# IgniterDriver.net
KiCad netlist of a schematic drawn in EAGLE
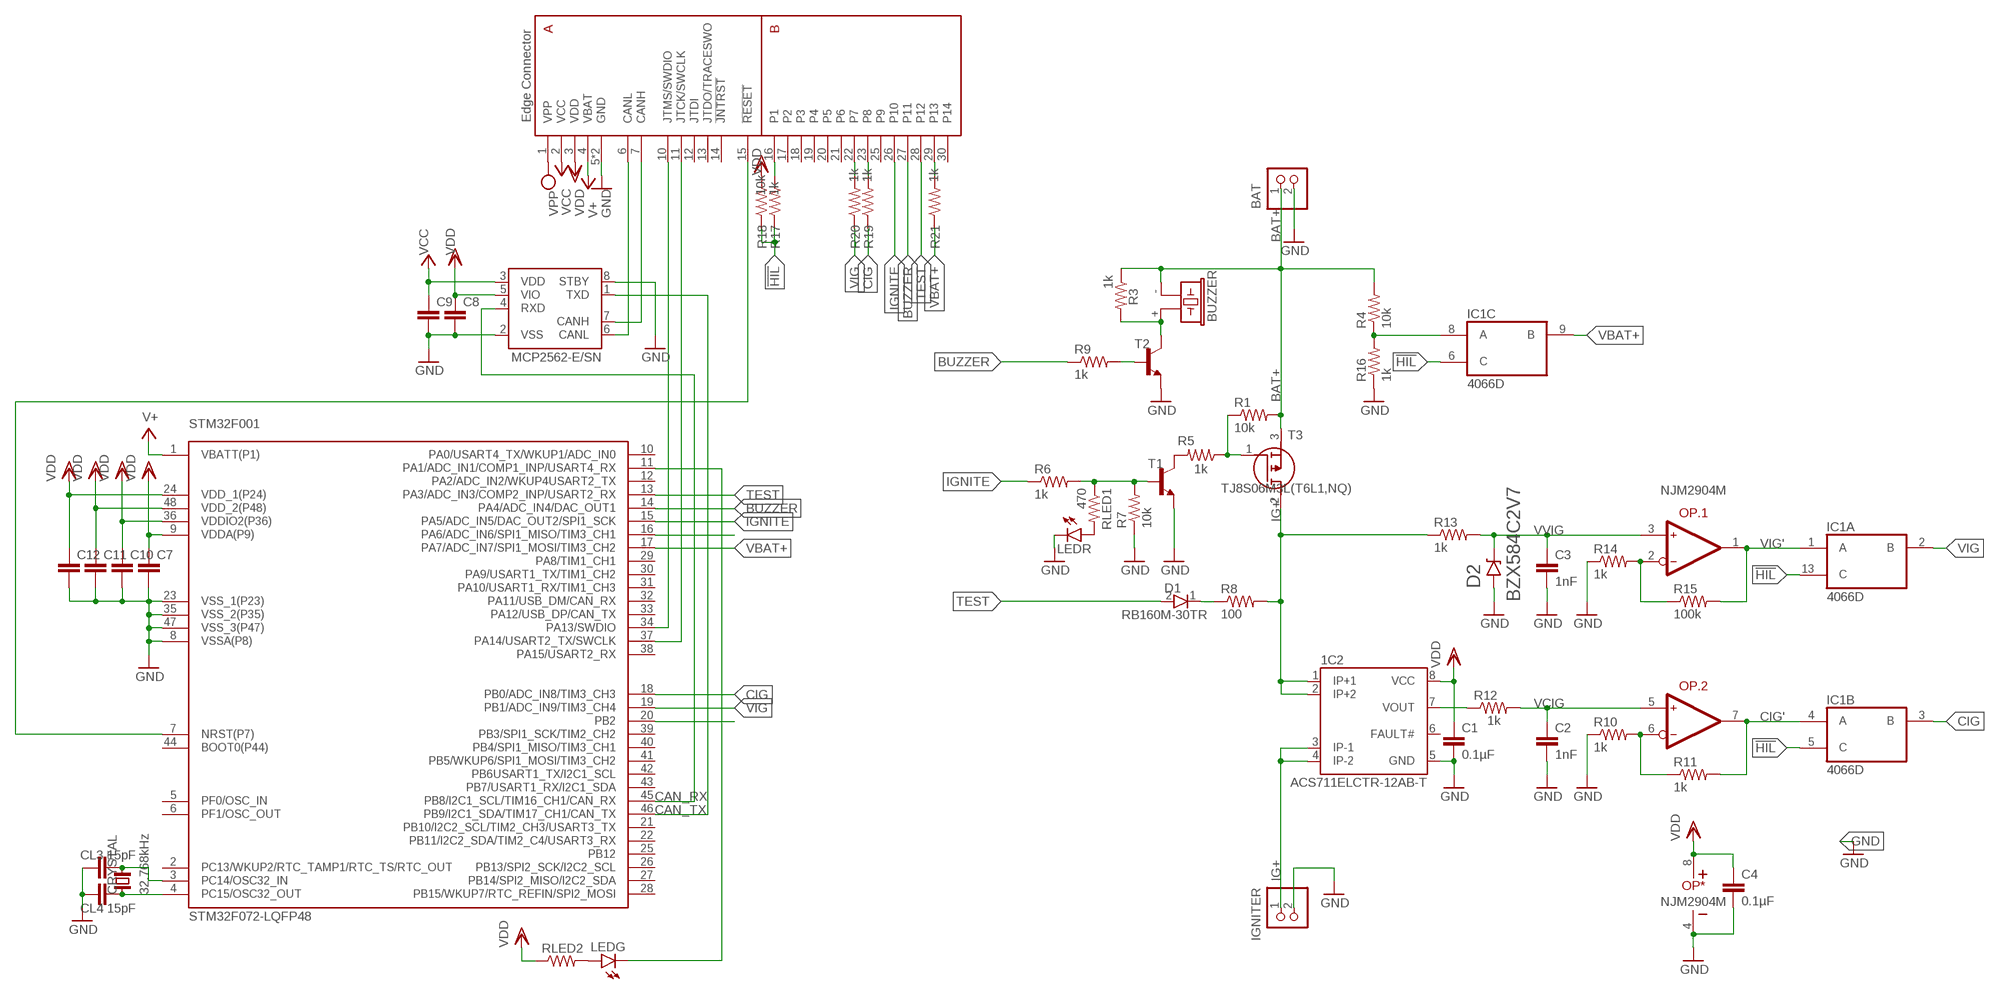
[diagram p0: schematic, sheet 1]

(export (version "E")
  (design (tool "Eeschema 10.0.6"))
  (components
    (comp (ref "1C2")
      (value "ACS711ELCTR-12AB-T")
      (footprint "eagle-import:SOIC8")
      (libsource (lib "eagle-import") (part "ACS711ELC?TR-12AB-T"))
    )
    (comp (ref "BAT")
      (value "S2B-XH-A")
      (footprint "eagle-import:S2B-XH-A")
      (libsource (lib "eagle-import") (part "S2B-XH-A"))
    )
    (comp (ref "BUZZER")
      (value "F/CM12P")
      (footprint "eagle-import:F_CM12P")
      (libsource (lib "eagle-import") (part "F/CM12P"))
    )
    (comp (ref "C1")
      (value "0.1µF")
      (footprint "eagle-import:C0603K")
      (libsource (lib "eagle-import") (part "C-EUC0603K"))
    )
    (comp (ref "C2")
      (value "1nF")
      (footprint "eagle-import:C0603K")
      (libsource (lib "eagle-import") (part "C-EUC0603K"))
    )
    (comp (ref "C3")
      (value "1nF")
      (footprint "eagle-import:C0603K")
      (libsource (lib "eagle-import") (part "C-EUC0603K"))
    )
    (comp (ref "C4")
      (value "0.1µF")
      (footprint "eagle-import:C0603K")
      (libsource (lib "eagle-import") (part "C-EUC0603K"))
    )
    (comp (ref "C7")
      (value "C-EUC0603K")
      (footprint "eagle-import:C0603K")
      (libsource (lib "eagle-import") (part "C-EUC0603K"))
    )
    (comp (ref "C8")
      (value "C-EUC0603K")
      (footprint "eagle-import:C0603K")
      (libsource (lib "eagle-import") (part "C-EUC0603K"))
    )
    (comp (ref "C9")
      (value "C-EUC0603K")
      (footprint "eagle-import:C0603K")
      (libsource (lib "eagle-import") (part "C-EUC0603K"))
    )
    (comp (ref "C10")
      (value "C-EUC0603K")
      (footprint "eagle-import:C0603K")
      (libsource (lib "eagle-import") (part "C-EUC0603K"))
    )
    (comp (ref "C11")
      (value "C-EUC0603K")
      (footprint "eagle-import:C0603K")
      (libsource (lib "eagle-import") (part "C-EUC0603K"))
    )
    (comp (ref "C12")
      (value "C-EUC0603K")
      (footprint "eagle-import:C0603K")
      (libsource (lib "eagle-import") (part "C-EUC0603K"))
    )
    (comp (ref "CL3")
      (value "15pF")
      (footprint "eagle-import:C0603K")
      (libsource (lib "eagle-import") (part "C-EUC0603K"))
    )
    (comp (ref "CL4")
      (value "15pF")
      (footprint "eagle-import:C0603K")
      (libsource (lib "eagle-import") (part "C-EUC0603K"))
    )
    (comp (ref "CRYSTAL")
      (value "32.768kHz")
      (footprint "eagle-import:FC-255")
      (libsource (lib "eagle-import") (part "CRYTALFC-255"))
    )
    (comp (ref "D1")
      (value "RB160M-30TR")
      (footprint "eagle-import:SODFL3516X90N")
      (fields (field (name "MOUSER_PART_NUMBER") "755-RB160M-30TR") (field (name "RS_PART_NUMBER") "7526079"))
      (libsource (lib "eagle-import") (part "RB160M-30TR"))
    )
    (comp (ref "D2")
      (value "BZX584C2V7")
      (footprint "eagle-import:BZX584C")
      (libsource (lib "eagle-import") (part "BZX584C"))
    )
    (comp (ref "IC1")
      (value "4066D")
      (footprint "eagle-import:SO14")
      (libsource (lib "eagle-import") (part "4066D"))
    )
    (comp (ref "IGNITER")
      (value "S2B-XH-A")
      (footprint "eagle-import:S2B-XH-A")
      (libsource (lib "eagle-import") (part "S2B-XH-A"))
    )
    (comp (ref "LEDG")
      (value "LEDCHIP-LED0603")
      (footprint "eagle-import:CHIP-LED0603")
      (libsource (lib "eagle-import") (part "LEDCHIP-LED0603"))
    )
    (comp (ref "LEDR")
      (value "LEDCHIPLED_0603")
      (footprint "eagle-import:CHIPLED_0603")
      (libsource (lib "eagle-import") (part "LEDCHIPLED_0603"))
    )
    (comp (ref "MCP2562")
      (value "MCP2562-E/SN")
      (footprint "eagle-import:SOIC127P600X175-8N")
      (fields (field (name "MF") "Microchip"))
      (libsource (lib "eagle-import") (part "MCP2562-E/SN"))
    )
    (comp (ref "OP")
      (value "NJM2904M")
      (footprint "eagle-import:SO-8")
      (libsource (lib "eagle-import") (part "NJM2904M"))
    )
    (comp (ref "R1")
      (value "10k")
      (footprint "eagle-import:R0603")
      (libsource (lib "eagle-import") (part "R-US_R0603"))
    )
    (comp (ref "R3")
      (value "1k")
      (footprint "eagle-import:R0603")
      (libsource (lib "eagle-import") (part "R-US_R0603"))
    )
    (comp (ref "R4")
      (value "10k")
      (footprint "eagle-import:R0603")
      (libsource (lib "eagle-import") (part "R-US_R0603"))
    )
    (comp (ref "R5")
      (value "1k")
      (footprint "eagle-import:R0603")
      (libsource (lib "eagle-import") (part "R-US_R0603"))
    )
    (comp (ref "R6")
      (value "1k")
      (footprint "eagle-import:R0603")
      (libsource (lib "eagle-import") (part "R-US_R0603"))
    )
    (comp (ref "R7")
      (value "10k")
      (footprint "eagle-import:R0603")
      (libsource (lib "eagle-import") (part "R-US_R0603"))
    )
    (comp (ref "R8")
      (value "100")
      (footprint "eagle-import:R0603")
      (libsource (lib "eagle-import") (part "R-US_R0603"))
    )
    (comp (ref "R9")
      (value "1k")
      (footprint "eagle-import:R0603")
      (libsource (lib "eagle-import") (part "R-US_R0603"))
    )
    (comp (ref "R10")
      (value "1k")
      (footprint "eagle-import:R0603")
      (libsource (lib "eagle-import") (part "R-US_R0603"))
    )
    (comp (ref "R11")
      (value "1k")
      (footprint "eagle-import:R0603")
      (libsource (lib "eagle-import") (part "R-US_R0603"))
    )
    (comp (ref "R12")
      (value "1k")
      (footprint "eagle-import:R0603")
      (libsource (lib "eagle-import") (part "R-US_R0603"))
    )
    (comp (ref "R13")
      (value "1k")
      (footprint "eagle-import:R0603")
      (libsource (lib "eagle-import") (part "R-US_R0603"))
    )
    (comp (ref "R14")
      (value "1k")
      (footprint "eagle-import:R0603")
      (libsource (lib "eagle-import") (part "R-US_R0603"))
    )
    (comp (ref "R15")
      (value "100k")
      (footprint "eagle-import:R0603")
      (libsource (lib "eagle-import") (part "R-US_R0603"))
    )
    (comp (ref "R16")
      (value "1k")
      (footprint "eagle-import:R0603")
      (libsource (lib "eagle-import") (part "R-US_R0603"))
    )
    (comp (ref "R17")
      (value "1k")
      (footprint "eagle-import:R0603")
      (libsource (lib "eagle-import") (part "R-US_R0603"))
    )
    (comp (ref "R18")
      (value "10k")
      (footprint "eagle-import:R0603")
      (libsource (lib "eagle-import") (part "R-US_R0603"))
    )
    (comp (ref "R19")
      (value "1k")
      (footprint "eagle-import:R0603")
      (libsource (lib "eagle-import") (part "resistor_348_R-US_R0603"))
    )
    (comp (ref "R20")
      (value "1k")
      (footprint "eagle-import:R0603")
      (libsource (lib "eagle-import") (part "resistor_348_R-US_R0603"))
    )
    (comp (ref "R21")
      (value "1k")
      (footprint "eagle-import:R0603")
      (libsource (lib "eagle-import") (part "resistor_348_R-US_R0603"))
    )
    (comp (ref "RLED1")
      (value "470")
      (footprint "eagle-import:R0603")
      (libsource (lib "eagle-import") (part "R-US_R0603"))
    )
    (comp (ref "RLED2")
      (value "R-US_R0603")
      (footprint "eagle-import:R0603")
      (libsource (lib "eagle-import") (part "R-US_R0603"))
    )
    (comp (ref "STM32F001")
      (value "STM32F072-LQFP48")
      (footprint "eagle-import:LQFP48")
      (libsource (lib "eagle-import") (part "STM32F072-LQFP48"))
    )
    (comp (ref "T1")
      (value "-NPN-SOT23-EBC")
      (footprint "eagle-import:SOT23-EBC")
      (libsource (lib "eagle-import") (part "-NPN-SOT23-EBC"))
    )
    (comp (ref "T2")
      (value "-NPN-SOT23-EBC")
      (footprint "eagle-import:SOT23-EBC")
      (libsource (lib "eagle-import") (part "-NPN-SOT23-EBC"))
    )
    (comp (ref "T3")
      (value "TJ8S06M3L(T6L1,NQ)")
      (footprint "eagle-import:TJ8S06M3LT6L1NQ")
      (fields (field (name "MOUSER_PART_NUMBER") "757-TJ8S06M3LT6L1NQ"))
      (libsource (lib "eagle-import") (part "TJ8S06M3L(T6L1,NQ)"))
    )
    (comp (ref "U$2")
      (value "EDGE30")
      (footprint "eagle-import:EDGE30")
      (libsource (lib "eagle-import") (part "EDGE30"))
    )
  )
  (nets
    (net (code "1") (name "/BAT+") (class "Default")
      (node (ref "BAT") (pin "1") (pinfunction "1_1") (pintype "passive"))
      (node (ref "BUZZER") (pin "-") (pinfunction "2_-") (pintype "passive"))
      (node (ref "R1") (pin "2") (pinfunction "2_2") (pintype "passive"))
      (node (ref "R3") (pin "1") (pinfunction "1_1") (pintype "passive"))
      (node (ref "R4") (pin "2") (pinfunction "2_2") (pintype "passive"))
      (node (ref "T3") (pin "3") (pinfunction "S_3") (pintype "bidirectional"))
    )
    (net (code "2") (name "/CAN_RX") (class "Default")
      (node (ref "MCP2562") (pin "4") (pinfunction "RXD_4") (pintype "output"))
      (node (ref "STM32F001") (pin "45") (pinfunction "PB8/I2C1_SCL/TIM16_CH1/CAN_RX_45") (pintype "bidirectional"))
    )
    (net (code "3") (name "/CAN_TX") (class "Default")
      (node (ref "MCP2562") (pin "1") (pinfunction "TXD_1") (pintype "input"))
      (node (ref "STM32F001") (pin "46") (pinfunction "PB9/I2C1_SDA/TIM17_CH1/CAN_TX_46") (pintype "bidirectional"))
    )
    (net (code "4") (name "/CIG'") (class "Default")
      (node (ref "IC1") (pin "4") (pinfunction "A_4") (pintype "tri_state"))
      (node (ref "OP") (pin "7") (pinfunction "OUT_7") (pintype "output"))
      (node (ref "R11") (pin "2") (pinfunction "2_2") (pintype "passive"))
    )
    (net (code "5") (name "/IG+") (class "Default")
      (node (ref "1C2") (pin "3") (pinfunction "IP-1_3") (pintype "bidirectional"))
      (node (ref "1C2") (pin "4") (pinfunction "IP-2_4") (pintype "bidirectional"))
      (node (ref "IGNITER") (pin "1") (pinfunction "1_1") (pintype "passive"))
    )
    (net (code "6") (name "/IG+'") (class "Default")
      (node (ref "1C2") (pin "1") (pinfunction "IP+1_1") (pintype "bidirectional"))
      (node (ref "1C2") (pin "2") (pinfunction "IP+2_2") (pintype "bidirectional"))
      (node (ref "R13") (pin "1") (pinfunction "1_1") (pintype "passive"))
      (node (ref "R8") (pin "2") (pinfunction "2_2") (pintype "passive"))
      (node (ref "T3") (pin "2") (pinfunction "D_2") (pintype "bidirectional"))
    )
    (net (code "7") (name "/VCIG") (class "Default")
      (node (ref "C2") (pin "1") (pinfunction "1_1") (pintype "passive"))
      (node (ref "OP") (pin "5") (pinfunction "IN+_5") (pintype "input"))
      (node (ref "R12") (pin "2") (pinfunction "2_2") (pintype "passive"))
    )
    (net (code "8") (name "/VIG'") (class "Default")
      (node (ref "IC1") (pin "1") (pinfunction "A_1") (pintype "tri_state"))
      (node (ref "OP") (pin "1") (pinfunction "OUT_1") (pintype "output"))
      (node (ref "R15") (pin "2") (pinfunction "2_2") (pintype "passive"))
    )
    (net (code "9") (name "/VVIG") (class "Default")
      (node (ref "C3") (pin "1") (pinfunction "1_1") (pintype "passive"))
      (node (ref "D2") (pin "C") (pinfunction "C_C") (pintype "bidirectional"))
      (node (ref "OP") (pin "3") (pinfunction "IN+_3") (pintype "input"))
      (node (ref "R13") (pin "2") (pinfunction "2_2") (pintype "passive"))
    )
    (net (code "10") (name "/~{HIL}") (class "Default")
      (node (ref "IC1") (pin "13") (pinfunction "C_13") (pintype "input"))
      (node (ref "IC1") (pin "5") (pinfunction "C_5") (pintype "input"))
      (node (ref "IC1") (pin "6") (pinfunction "C_6") (pintype "input"))
      (node (ref "R17") (pin "1") (pinfunction "1_1") (pintype "passive"))
      (node (ref "R18") (pin "1") (pinfunction "1_1") (pintype "passive"))
    )
    (net (code "11") (name "BUZZER") (class "Default")
      (node (ref "R9") (pin "1") (pinfunction "1_1") (pintype "passive"))
      (node (ref "STM32F001") (pin "14") (pinfunction "PA4/ADC_IN4/DAC_OUT1_14") (pintype "bidirectional"))
      (node (ref "U$2") (pin "27") (pinfunction "P11_27") (pintype "bidirectional"))
    )
    (net (code "12") (name "CIG") (class "Default")
      (node (ref "IC1") (pin "3") (pinfunction "B_3") (pintype "tri_state"))
      (node (ref "R19") (pin "1") (pinfunction "1_1") (pintype "passive"))
      (node (ref "STM32F001") (pin "18") (pinfunction "PB0/ADC_IN8/TIM3_CH3_18") (pintype "bidirectional"))
    )
    (net (code "13") (name "GND") (class "Default")
      (node (ref "1C2") (pin "5") (pinfunction "GND_5") (pintype "bidirectional"))
      (node (ref "BAT") (pin "2") (pinfunction "2_2") (pintype "passive"))
      (node (ref "C1") (pin "2") (pinfunction "2_2") (pintype "passive"))
      (node (ref "C10") (pin "2") (pinfunction "2_2") (pintype "passive"))
      (node (ref "C11") (pin "2") (pinfunction "2_2") (pintype "passive"))
      (node (ref "C12") (pin "2") (pinfunction "2_2") (pintype "passive"))
      (node (ref "C2") (pin "2") (pinfunction "2_2") (pintype "passive"))
      (node (ref "C3") (pin "2") (pinfunction "2_2") (pintype "passive"))
      (node (ref "C4") (pin "2") (pinfunction "2_2") (pintype "passive"))
      (node (ref "C7") (pin "2") (pinfunction "2_2") (pintype "passive"))
      (node (ref "C8") (pin "2") (pinfunction "2_2") (pintype "passive"))
      (node (ref "C9") (pin "2") (pinfunction "2_2") (pintype "passive"))
      (node (ref "CL3") (pin "1") (pinfunction "1_1") (pintype "passive"))
      (node (ref "CL4") (pin "1") (pinfunction "1_1") (pintype "passive"))
      (node (ref "D2") (pin "A") (pinfunction "A_A") (pintype "bidirectional"))
      (node (ref "IGNITER") (pin "2") (pinfunction "2_2") (pintype "passive"))
      (node (ref "LEDR") (pin "C") (pinfunction "C_C") (pintype "passive"))
      (node (ref "MCP2562") (pin "2") (pinfunction "VSS_2") (pintype "power_in"))
      (node (ref "MCP2562") (pin "8") (pinfunction "STBY_8") (pintype "input"))
      (node (ref "OP") (pin "4") (pinfunction "V-_4") (pintype "power_in"))
      (node (ref "R10") (pin "1") (pinfunction "1_1") (pintype "passive"))
      (node (ref "R14") (pin "1") (pinfunction "1_1") (pintype "passive"))
      (node (ref "R16") (pin "1") (pinfunction "1_1") (pintype "passive"))
      (node (ref "R7") (pin "1") (pinfunction "1_1") (pintype "passive"))
      (node (ref "STM32F001") (pin "23") (pinfunction "VSS_1(P23)_23") (pintype "bidirectional"))
      (node (ref "STM32F001") (pin "35") (pinfunction "VSS_2(P35)_35") (pintype "bidirectional"))
      (node (ref "STM32F001") (pin "47") (pinfunction "VSS_3(P47)_47") (pintype "bidirectional"))
      (node (ref "STM32F001") (pin "8") (pinfunction "VSSA(P8)_8") (pintype "bidirectional"))
      (node (ref "T1") (pin "E") (pinfunction "E_E") (pintype "passive"))
      (node (ref "T2") (pin "E") (pinfunction "E_E") (pintype "passive"))
      (node (ref "U$2") (pin "5") (pinfunction "GND_5") (pintype "power_in"))
      (node (ref "U$2") (pin "8") (pinfunction "GND_8") (pintype "power_in"))
    )
    (net (code "14") (name "IGNITE") (class "Default")
      (node (ref "R6") (pin "1") (pinfunction "1_1") (pintype "passive"))
      (node (ref "STM32F001") (pin "15") (pinfunction "PA5/ADC_IN5/DAC_OUT2/SPI1_SCK_15") (pintype "bidirectional"))
      (node (ref "U$2") (pin "26") (pinfunction "P10_26") (pintype "bidirectional"))
    )
    (net (code "15") (name "Net-(1C2-VOUT)") (class "Default")
      (node (ref "1C2") (pin "7") (pinfunction "VOUT_7") (pintype "bidirectional"))
      (node (ref "R12") (pin "1") (pinfunction "1_1") (pintype "passive"))
    )
    (net (code "16") (name "Net-(BUZZER-1)") (class "Default")
      (node (ref "BUZZER") (pin "+") (pinfunction "1_+") (pintype "passive"))
      (node (ref "R3") (pin "2") (pinfunction "2_2") (pintype "passive"))
      (node (ref "T2") (pin "C") (pinfunction "C_C") (pintype "passive"))
    )
    (net (code "17") (name "Net-(D1-K)") (class "Default")
      (node (ref "D1") (pin "1") (pinfunction "K_1") (pintype "bidirectional"))
      (node (ref "R8") (pin "1") (pinfunction "1_1") (pintype "passive"))
    )
    (net (code "18") (name "Net-(IC1C-A)") (class "Default")
      (node (ref "IC1") (pin "8") (pinfunction "A_8") (pintype "tri_state"))
      (node (ref "R16") (pin "2") (pinfunction "2_2") (pintype "passive"))
      (node (ref "R4") (pin "1") (pinfunction "1_1") (pintype "passive"))
    )
    (net (code "19") (name "Net-(LEDG-PadA)") (class "Default")
      (node (ref "LEDG") (pin "A") (pinfunction "A_A") (pintype "passive"))
      (node (ref "RLED2") (pin "2") (pinfunction "2_2") (pintype "passive"))
    )
    (net (code "20") (name "Net-(LEDR-PadA)") (class "Default")
      (node (ref "LEDR") (pin "A") (pinfunction "A_A") (pintype "passive"))
      (node (ref "RLED1") (pin "2") (pinfunction "2_2") (pintype "passive"))
    )
    (net (code "21") (name "Net-(MCP2562-CANH)") (class "Default")
      (node (ref "MCP2562") (pin "7") (pinfunction "CANH_7") (pintype "input"))
      (node (ref "U$2") (pin "7") (pinfunction "CANH_7") (pintype "bidirectional"))
    )
    (net (code "22") (name "Net-(MCP2562-CANL)") (class "Default")
      (node (ref "MCP2562") (pin "6") (pinfunction "CANL_6") (pintype "input"))
      (node (ref "U$2") (pin "6") (pinfunction "CANL_6") (pintype "bidirectional"))
    )
    (net (code "23") (name "Net-(OPB-IN-)") (class "Default")
      (node (ref "OP") (pin "2") (pinfunction "IN-_2") (pintype "input"))
      (node (ref "R14") (pin "2") (pinfunction "2_2") (pintype "passive"))
      (node (ref "R15") (pin "1") (pinfunction "1_1") (pintype "passive"))
    )
    (net (code "24") (name "Net-(OPC-IN-)") (class "Default")
      (node (ref "OP") (pin "6") (pinfunction "IN-_6") (pintype "input"))
      (node (ref "R10") (pin "2") (pinfunction "2_2") (pintype "passive"))
      (node (ref "R11") (pin "1") (pinfunction "1_1") (pintype "passive"))
    )
    (net (code "25") (name "Net-(R5-Pad2)") (class "Default")
      (node (ref "R5") (pin "2") (pinfunction "2_2") (pintype "passive"))
      (node (ref "T1") (pin "C") (pinfunction "C_C") (pintype "passive"))
    )
    (net (code "26") (name "Net-(R6-Pad2)") (class "Default")
      (node (ref "R6") (pin "2") (pinfunction "2_2") (pintype "passive"))
      (node (ref "R7") (pin "2") (pinfunction "2_2") (pintype "passive"))
      (node (ref "RLED1") (pin "1") (pinfunction "1_1") (pintype "passive"))
      (node (ref "T1") (pin "B") (pinfunction "B_B") (pintype "passive"))
    )
    (net (code "27") (name "Net-(R9-Pad2)") (class "Default")
      (node (ref "R9") (pin "2") (pinfunction "2_2") (pintype "passive"))
      (node (ref "T2") (pin "B") (pinfunction "B_B") (pintype "passive"))
    )
    (net (code "28") (name "Net-(STM32F001-NRST(P7))") (class "Default")
      (node (ref "STM32F001") (pin "7") (pinfunction "NRST(P7)_7") (pintype "bidirectional"))
      (node (ref "U$2") (pin "15") (pinfunction "~{RESET}_15") (pintype "bidirectional"))
    )
    (net (code "29") (name "Net-(STM32F001-PA1{slash}ADC_IN1{slash}COMP1_INP{slash}USART4_RX)") (class "Default")
      (node (ref "LEDG") (pin "C") (pinfunction "C_C") (pintype "passive"))
      (node (ref "STM32F001") (pin "11") (pinfunction "PA1/ADC_IN1/COMP1_INP/USART4_RX_11") (pintype "bidirectional"))
    )
    (net (code "30") (name "Net-(STM32F001-PA13{slash}SWDIO)") (class "Default")
      (node (ref "STM32F001") (pin "34") (pinfunction "PA13/SWDIO_34") (pintype "bidirectional"))
      (node (ref "U$2") (pin "10") (pinfunction "JTMS/SWDIO_10") (pintype "bidirectional"))
    )
    (net (code "31") (name "Net-(STM32F001-PA14{slash}USART2_TX{slash}SWCLK)") (class "Default")
      (node (ref "STM32F001") (pin "37") (pinfunction "PA14/USART2_TX/SWCLK_37") (pintype "bidirectional"))
      (node (ref "U$2") (pin "11") (pinfunction "JTCK/SWCLK_11") (pintype "bidirectional"))
    )
    (net (code "32") (name "Net-(STM32F001-PC14{slash}OSC32_IN)") (class "Default")
      (node (ref "CL3") (pin "2") (pinfunction "2_2") (pintype "passive"))
      (node (ref "CRYSTAL") (pin "2") (pinfunction "2_2") (pintype "passive"))
      (node (ref "STM32F001") (pin "3") (pinfunction "PC14/OSC32_IN_3") (pintype "bidirectional"))
    )
    (net (code "33") (name "Net-(STM32F001-PC15{slash}OSC32_OUT)") (class "Default")
      (node (ref "CL4") (pin "2") (pinfunction "2_2") (pintype "passive"))
      (node (ref "CRYSTAL") (pin "1") (pinfunction "1_1") (pintype "passive"))
      (node (ref "STM32F001") (pin "4") (pinfunction "PC15/OSC32_OUT_4") (pintype "bidirectional"))
    )
    (net (code "34") (name "Net-(T3-G)") (class "Default")
      (node (ref "R1") (pin "1") (pinfunction "1_1") (pintype "passive"))
      (node (ref "R5") (pin "1") (pinfunction "1_1") (pintype "passive"))
      (node (ref "T3") (pin "1") (pinfunction "G_1") (pintype "bidirectional"))
    )
    (net (code "35") (name "Net-(U$2-P1)") (class "Default")
      (node (ref "R17") (pin "2") (pinfunction "2_2") (pintype "passive"))
      (node (ref "U$2") (pin "16") (pinfunction "P1_16") (pintype "bidirectional"))
    )
    (net (code "36") (name "Net-(U$2-P7)") (class "Default")
      (node (ref "R20") (pin "2") (pinfunction "2_2") (pintype "passive"))
      (node (ref "U$2") (pin "22") (pinfunction "P7_22") (pintype "bidirectional"))
    )
    (net (code "37") (name "Net-(U$2-P8)") (class "Default")
      (node (ref "R19") (pin "2") (pinfunction "2_2") (pintype "passive"))
      (node (ref "U$2") (pin "23") (pinfunction "P8_23") (pintype "bidirectional"))
    )
    (net (code "38") (name "Net-(U$2-P13)") (class "Default")
      (node (ref "R21") (pin "2") (pinfunction "2_2") (pintype "passive"))
      (node (ref "U$2") (pin "29") (pinfunction "P13_29") (pintype "bidirectional"))
    )
    (net (code "39") (name "TEST") (class "Default")
      (node (ref "D1") (pin "2") (pinfunction "A_2") (pintype "bidirectional"))
      (node (ref "STM32F001") (pin "13") (pinfunction "PA3/ADC_IN3/COMP2_INP/USART2_RX_13") (pintype "bidirectional"))
      (node (ref "U$2") (pin "28") (pinfunction "P12_28") (pintype "bidirectional"))
    )
    (net (code "40") (name "V+") (class "Default")
      (node (ref "STM32F001") (pin "1") (pinfunction "VBATT(P1)_1") (pintype "bidirectional"))
      (node (ref "U$2") (pin "4") (pinfunction "VBAT_4") (pintype "power_in"))
    )
    (net (code "41") (name "VBAT+") (class "Default")
      (node (ref "IC1") (pin "9") (pinfunction "B_9") (pintype "tri_state"))
      (node (ref "R21") (pin "1") (pinfunction "1_1") (pintype "passive"))
      (node (ref "STM32F001") (pin "17") (pinfunction "PA7/ADC_IN7/SPI1_MOSI/TIM3_CH2_17") (pintype "bidirectional"))
    )
    (net (code "42") (name "VCC") (class "Default")
      (node (ref "C9") (pin "1") (pinfunction "1_1") (pintype "passive"))
      (node (ref "MCP2562") (pin "3") (pinfunction "VDD_3") (pintype "power_in"))
      (node (ref "U$2") (pin "2") (pinfunction "VCC_2") (pintype "power_in"))
    )
    (net (code "43") (name "VDD") (class "Default")
      (node (ref "1C2") (pin "8") (pinfunction "VCC_8") (pintype "bidirectional"))
      (node (ref "C1") (pin "1") (pinfunction "1_1") (pintype "passive"))
      (node (ref "C10") (pin "1") (pinfunction "1_1") (pintype "passive"))
      (node (ref "C11") (pin "1") (pinfunction "1_1") (pintype "passive"))
      (node (ref "C12") (pin "1") (pinfunction "1_1") (pintype "passive"))
      (node (ref "C4") (pin "1") (pinfunction "1_1") (pintype "passive"))
      (node (ref "C7") (pin "1") (pinfunction "1_1") (pintype "passive"))
      (node (ref "C8") (pin "1") (pinfunction "1_1") (pintype "passive"))
      (node (ref "MCP2562") (pin "5") (pinfunction "VIO_5") (pintype "power_in"))
      (node (ref "OP") (pin "8") (pinfunction "V+_8") (pintype "power_in"))
      (node (ref "R18") (pin "2") (pinfunction "2_2") (pintype "passive"))
      (node (ref "RLED2") (pin "1") (pinfunction "1_1") (pintype "passive"))
      (node (ref "STM32F001") (pin "24") (pinfunction "VDD_1(P24)_24") (pintype "bidirectional"))
      (node (ref "STM32F001") (pin "36") (pinfunction "VDDIO2(P36)_36") (pintype "bidirectional"))
      (node (ref "STM32F001") (pin "48") (pinfunction "VDD_2(P48)_48") (pintype "bidirectional"))
      (node (ref "STM32F001") (pin "9") (pinfunction "VDDA(P9)_9") (pintype "bidirectional"))
      (node (ref "U$2") (pin "3") (pinfunction "VDD_3") (pintype "power_in"))
    )
    (net (code "44") (name "VIG") (class "Default")
      (node (ref "IC1") (pin "2") (pinfunction "B_2") (pintype "tri_state"))
      (node (ref "R20") (pin "1") (pinfunction "1_1") (pintype "passive"))
      (node (ref "STM32F001") (pin "19") (pinfunction "PB1/ADC_IN9/TIM3_CH4_19") (pintype "bidirectional"))
    )
    (net (code "45") (name "VPP") (class "Default")
      (node (ref "U$2") (pin "1") (pinfunction "VPP_1") (pintype "power_in"))
    )
    (net (code "46") (name "unconnected-(1C2-FAULT#-Pad6)") (class "Default")
      (node (ref "1C2") (pin "6") (pinfunction "FAULT#_6") (pintype "bidirectional"))
    )
    (net (code "47") (name "unconnected-(STM32F001-BOOT0(P44)-Pad44)") (class "Default")
      (node (ref "STM32F001") (pin "44") (pinfunction "BOOT0(P44)_44") (pintype "bidirectional"))
    )
    (net (code "48") (name "unconnected-(STM32F001-PA0{slash}USART4_TX{slash}WKUP1{slash}ADC_IN0-Pad10)") (class "Default")
      (node (ref "STM32F001") (pin "10") (pinfunction "PA0/USART4_TX/WKUP1/ADC_IN0_10") (pintype "bidirectional"))
    )
    (net (code "49") (name "unconnected-(STM32F001-PA2{slash}ADC_IN2{slash}WKUP4USART2_TX-Pad12)") (class "Default")
      (node (ref "STM32F001") (pin "12") (pinfunction "PA2/ADC_IN2/WKUP4USART2_TX_12") (pintype "bidirectional"))
    )
    (net (code "50") (name "unconnected-(STM32F001-PA6{slash}ADC_IN6{slash}SPI1_MISO{slash}TIM3_CH1-Pad16)") (class "Default")
      (node (ref "STM32F001") (pin "16") (pinfunction "PA6/ADC_IN6/SPI1_MISO/TIM3_CH1_16") (pintype "bidirectional"))
    )
    (net (code "51") (name "unconnected-(STM32F001-PA8{slash}TIM1_CH1-Pad29)") (class "Default")
      (node (ref "STM32F001") (pin "29") (pinfunction "PA8/TIM1_CH1_29") (pintype "bidirectional"))
    )
    (net (code "52") (name "unconnected-(STM32F001-PA9{slash}USART1_TX{slash}TIM1_CH2-Pad30)") (class "Default")
      (node (ref "STM32F001") (pin "30") (pinfunction "PA9/USART1_TX/TIM1_CH2_30") (pintype "bidirectional"))
    )
    (net (code "53") (name "unconnected-(STM32F001-PA10{slash}USART1_RX{slash}TIM1_CH3-Pad31)") (class "Default")
      (node (ref "STM32F001") (pin "31") (pinfunction "PA10/USART1_RX/TIM1_CH3_31") (pintype "bidirectional"))
    )
    (net (code "54") (name "unconnected-(STM32F001-PA11{slash}USB_DM{slash}CAN_RX-Pad32)") (class "Default")
      (node (ref "STM32F001") (pin "32") (pinfunction "PA11/USB_DM/CAN_RX_32") (pintype "bidirectional"))
    )
    (net (code "55") (name "unconnected-(STM32F001-PA12{slash}USB_DP{slash}CAN_TX-Pad33)") (class "Default")
      (node (ref "STM32F001") (pin "33") (pinfunction "PA12/USB_DP/CAN_TX_33") (pintype "bidirectional"))
    )
    (net (code "56") (name "unconnected-(STM32F001-PA15{slash}USART2_RX-Pad38)") (class "Default")
      (node (ref "STM32F001") (pin "38") (pinfunction "PA15/USART2_RX_38") (pintype "bidirectional"))
    )
    (net (code "57") (name "unconnected-(STM32F001-PB2-Pad20)") (class "Default")
      (node (ref "STM32F001") (pin "20") (pinfunction "PB2_20") (pintype "bidirectional"))
    )
    (net (code "58") (name "unconnected-(STM32F001-PB3{slash}SPI1_SCK{slash}TIM2_CH2-Pad39)") (class "Default")
      (node (ref "STM32F001") (pin "39") (pinfunction "PB3/SPI1_SCK/TIM2_CH2_39") (pintype "bidirectional"))
    )
    (net (code "59") (name "unconnected-(STM32F001-PB4{slash}SPI1_MISO{slash}TIM3_CH1-Pad40)") (class "Default")
      (node (ref "STM32F001") (pin "40") (pinfunction "PB4/SPI1_MISO/TIM3_CH1_40") (pintype "bidirectional"))
    )
    (net (code "60") (name "unconnected-(STM32F001-PB5{slash}WKUP6{slash}SPI1_MOSI{slash}TIM3_CH2-Pad41)") (class "Default")
      (node (ref "STM32F001") (pin "41") (pinfunction "PB5/WKUP6/SPI1_MOSI/TIM3_CH2_41") (pintype "bidirectional"))
    )
    (net (code "61") (name "unconnected-(STM32F001-PB6USART1_TX{slash}I2C1_SCL-Pad42)") (class "Default")
      (node (ref "STM32F001") (pin "42") (pinfunction "PB6USART1_TX/I2C1_SCL_42") (pintype "bidirectional"))
    )
    (net (code "62") (name "unconnected-(STM32F001-PB7{slash}USART1_RX{slash}I2C1_SDA-Pad43)") (class "Default")
      (node (ref "STM32F001") (pin "43") (pinfunction "PB7/USART1_RX/I2C1_SDA_43") (pintype "bidirectional"))
    )
    (net (code "63") (name "unconnected-(STM32F001-PB10{slash}I2C2_SCL{slash}TIM2_CH3{slash}USART3_TX-Pad21)") (class "Default")
      (node (ref "STM32F001") (pin "21") (pinfunction "PB10/I2C2_SCL/TIM2_CH3/USART3_TX_21") (pintype "bidirectional"))
    )
    (net (code "64") (name "unconnected-(STM32F001-PB11{slash}I2C2_SDA{slash}TIM2_C4{slash}USART3_RX-Pad22)") (class "Default")
      (node (ref "STM32F001") (pin "22") (pinfunction "PB11/I2C2_SDA/TIM2_C4/USART3_RX_22") (pintype "bidirectional"))
    )
    (net (code "65") (name "unconnected-(STM32F001-PB12-Pad25)") (class "Default")
      (node (ref "STM32F001") (pin "25") (pinfunction "PB12_25") (pintype "bidirectional"))
    )
    (net (code "66") (name "unconnected-(STM32F001-PB13{slash}SPI2_SCK{slash}I2C2_SCL-Pad26)") (class "Default")
      (node (ref "STM32F001") (pin "26") (pinfunction "PB13/SPI2_SCK/I2C2_SCL_26") (pintype "bidirectional"))
    )
    (net (code "67") (name "unconnected-(STM32F001-PB14{slash}SPI2_MISO{slash}I2C2_SDA-Pad27)") (class "Default")
      (node (ref "STM32F001") (pin "27") (pinfunction "PB14/SPI2_MISO/I2C2_SDA_27") (pintype "bidirectional"))
    )
    (net (code "68") (name "unconnected-(STM32F001-PB15{slash}WKUP7{slash}RTC_REFIN{slash}SPI2_MOSI-Pad28)") (class "Default")
      (node (ref "STM32F001") (pin "28") (pinfunction "PB15/WKUP7/RTC_REFIN/SPI2_MOSI_28") (pintype "bidirectional"))
    )
    (net (code "69") (name "unconnected-(STM32F001-PC13{slash}WKUP2{slash}RTC_TAMP1{slash}RTC_TS{slash}RTC_OUT-Pad2)") (class "Default")
      (node (ref "STM32F001") (pin "2") (pinfunction "PC13/WKUP2/RTC_TAMP1/RTC_TS/RTC_OUT_2") (pintype "bidirectional"))
    )
    (net (code "70") (name "unconnected-(STM32F001-PF0{slash}OSC_IN-Pad5)") (class "Default")
      (node (ref "STM32F001") (pin "5") (pinfunction "PF0/OSC_IN_5") (pintype "bidirectional"))
    )
    (net (code "71") (name "unconnected-(STM32F001-PF1{slash}OSC_OUT-Pad6)") (class "Default")
      (node (ref "STM32F001") (pin "6") (pinfunction "PF1/OSC_OUT_6") (pintype "bidirectional"))
    )
    (net (code "72") (name "unconnected-(U$2-JTDI-Pad12)") (class "Default")
      (node (ref "U$2") (pin "12") (pinfunction "JTDI_12") (pintype "bidirectional"))
    )
    (net (code "73") (name "unconnected-(U$2-JTDO{slash}TRACESWO-Pad13)") (class "Default")
      (node (ref "U$2") (pin "13") (pinfunction "JTDO/TRACESWO_13") (pintype "bidirectional"))
    )
    (net (code "74") (name "unconnected-(U$2-P2-Pad17)") (class "Default")
      (node (ref "U$2") (pin "17") (pinfunction "P2_17") (pintype "bidirectional"))
    )
    (net (code "75") (name "unconnected-(U$2-P3-Pad18)") (class "Default")
      (node (ref "U$2") (pin "18") (pinfunction "P3_18") (pintype "bidirectional"))
    )
    (net (code "76") (name "unconnected-(U$2-P4-Pad19)") (class "Default")
      (node (ref "U$2") (pin "19") (pinfunction "P4_19") (pintype "bidirectional"))
    )
    (net (code "77") (name "unconnected-(U$2-P5-Pad20)") (class "Default")
      (node (ref "U$2") (pin "20") (pinfunction "P5_20") (pintype "bidirectional"))
    )
    (net (code "78") (name "unconnected-(U$2-P6-Pad21)") (class "Default")
      (node (ref "U$2") (pin "21") (pinfunction "P6_21") (pintype "bidirectional"))
    )
    (net (code "79") (name "unconnected-(U$2-P9-Pad25)") (class "Default")
      (node (ref "U$2") (pin "25") (pinfunction "P9_25") (pintype "bidirectional"))
    )
    (net (code "80") (name "unconnected-(U$2-P14-Pad30)") (class "Default")
      (node (ref "U$2") (pin "30") (pinfunction "P14_30") (pintype "bidirectional"))
    )
    (net (code "81") (name "unconnected-(U$2-~{JNTRST}-Pad14)") (class "Default")
      (node (ref "U$2") (pin "14") (pinfunction "~{JNTRST}_14") (pintype "bidirectional"))
    )
  )
)
